# main.net
KiCad netlist of a schematic drawn in EAGLE
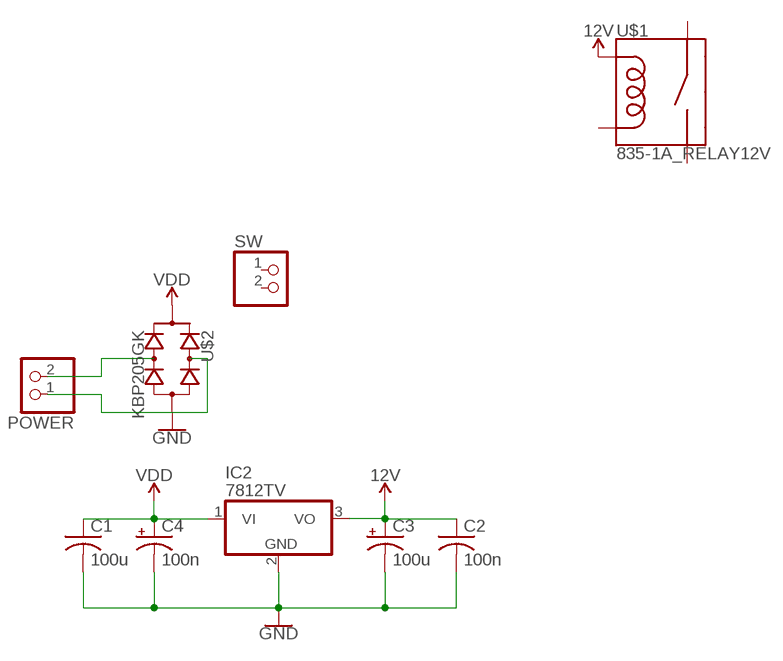
[diagram p0: schematic, sheet 1]

(export (version "E")
  (design (tool "Eeschema 10.0.6"))
  (components
    (comp (ref "C1")
      (value "100u")
      (footprint "eagle-import:C025-025X050")
      (libsource (lib "eagle-import") (part "C-US025-025X050"))
    )
    (comp (ref "C2")
      (value "100n")
      (footprint "eagle-import:C025-025X050")
      (libsource (lib "eagle-import") (part "C-US025-025X050"))
    )
    (comp (ref "C3")
      (value "100u")
      (footprint "eagle-import:E2-5")
      (libsource (lib "eagle-import") (part "CPOL-USE2-5"))
    )
    (comp (ref "C4")
      (value "100n")
      (footprint "eagle-import:E2-5")
      (libsource (lib "eagle-import") (part "CPOL-USE2-5"))
    )
    (comp (ref "IC2")
      (value "7812TV")
      (footprint "eagle-import:TO220V")
      (libsource (lib "eagle-import") (part "78TV12"))
    )
    (comp (ref "POWER")
      (value "PINHD-1X2")
      (footprint "eagle-import:1X02")
      (libsource (lib "eagle-import") (part "PINHD-1X2"))
    )
    (comp (ref "SW")
      (value "PINHD-1X2")
      (footprint "eagle-import:1X02")
      (libsource (lib "eagle-import") (part "PINHD-1X2"))
    )
    (comp (ref "U$1")
      (value "835-1A_RELAY12V")
      (footprint "eagle-import:835-1A_RELAY_12V")
      (libsource (lib "eagle-import") (part "835-1A_RELAY12V"))
    )
    (comp (ref "U$2")
      (value "KBP205GK")
      (footprint "eagle-import:KBP205G")
      (libsource (lib "eagle-import") (part "KBP205GK"))
    )
  )
  (nets
    (net (code "1") (name "12V") (class "Default")
      (node (ref "C2") (pin "1") (pinfunction "1_1") (pintype "passive"))
      (node (ref "C3") (pin "+") (pinfunction "+_+") (pintype "passive"))
      (node (ref "IC2") (pin "3") (pinfunction "VO_3") (pintype "passive"))
      (node (ref "U$1") (pin "P$1") (pinfunction "COIL1_P$1") (pintype "bidirectional"))
    )
    (net (code "2") (name "GND") (class "Default")
      (node (ref "C1") (pin "2") (pinfunction "2_2") (pintype "passive"))
      (node (ref "C2") (pin "2") (pinfunction "2_2") (pintype "passive"))
      (node (ref "C3") (pin "-") (pinfunction "-_-") (pintype "passive"))
      (node (ref "C4") (pin "-") (pinfunction "-_-") (pintype "passive"))
      (node (ref "IC2") (pin "2") (pinfunction "GND_2") (pintype "passive"))
      (node (ref "U$2") (pin "-") (pinfunction "-_-") (pintype "passive"))
    )
    (net (code "3") (name "Net-(POWER-Pad1)") (class "Default")
      (node (ref "POWER") (pin "1") (pinfunction "1_1") (pintype "passive"))
      (node (ref "U$2") (pin "AC@1") (pinfunction "AC_AC@1") (pintype "passive"))
    )
    (net (code "4") (name "Net-(POWER-Pad2)") (class "Default")
      (node (ref "POWER") (pin "2") (pinfunction "2_2") (pintype "passive"))
      (node (ref "U$2") (pin "AC@2") (pinfunction "AC_AC@2") (pintype "passive"))
    )
    (net (code "5") (name "VDD") (class "Default")
      (node (ref "C1") (pin "1") (pinfunction "1_1") (pintype "passive"))
      (node (ref "C4") (pin "+") (pinfunction "+_+") (pintype "passive"))
      (node (ref "IC2") (pin "1") (pinfunction "VI_1") (pintype "input"))
      (node (ref "U$2") (pin "+") (pinfunction "+_+") (pintype "passive"))
    )
    (net (code "6") (name "unconnected-(SW-Pad1)") (class "Default")
      (node (ref "SW") (pin "1") (pinfunction "1_1") (pintype "passive"))
    )
    (net (code "7") (name "unconnected-(SW-Pad2)") (class "Default")
      (node (ref "SW") (pin "2") (pinfunction "2_2") (pintype "passive"))
    )
    (net (code "8") (name "unconnected-(U$1-COIL2-PadP$2)") (class "Default")
      (node (ref "U$1") (pin "P$2") (pinfunction "COIL2_P$2") (pintype "bidirectional"))
    )
    (net (code "9") (name "unconnected-(U$1-MAIN-PadP$3)") (class "Default")
      (node (ref "U$1") (pin "P$3") (pinfunction "MAIN_P$3") (pintype "bidirectional"))
    )
    (net (code "10") (name "unconnected-(U$1-NO-PadP$4)") (class "Default")
      (node (ref "U$1") (pin "P$4") (pinfunction "NO_P$4") (pintype "bidirectional"))
    )
  )
)
